# az_vert_evef.net
KiCad netlist of a schematic drawn in EAGLE
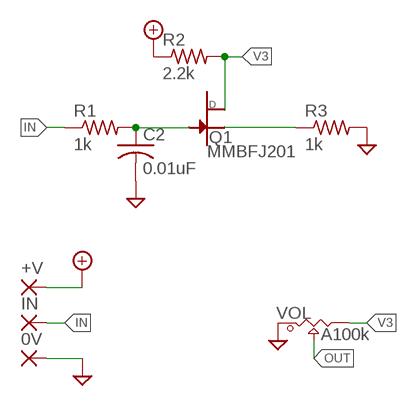
[diagram p0: schematic, sheet 1]

(export (version "E")
  (design (tool "Eeschema 10.0.6"))
  (components
    (comp (ref "+V")
      (value "SMD2")
      (footprint "eagle-import:SMD1,27-2,54")
      (libsource (lib "eagle-import") (part "SMD2"))
    )
    (comp (ref "0V")
      (value "SMD2")
      (footprint "eagle-import:SMD1,27-2,54")
      (libsource (lib "eagle-import") (part "SMD2"))
    )
    (comp (ref "C2")
      (value "0.01uF")
      (footprint "eagle-import:C0603")
      (libsource (lib "eagle-import") (part "C-USC0603"))
    )
    (comp (ref "IN")
      (value "SMD2")
      (footprint "eagle-import:SMD1,27-2,54")
      (libsource (lib "eagle-import") (part "SMD2"))
    )
    (comp (ref "Q1")
      (value "MMBFJ201")
      (footprint "eagle-import:MMBFJ201")
      (libsource (lib "eagle-import") (part "MMBFJ201"))
    )
    (comp (ref "R1")
      (value "1k")
      (footprint "eagle-import:R0603")
      (libsource (lib "eagle-import") (part "R-US_R0603"))
    )
    (comp (ref "R2")
      (value "2.2k")
      (footprint "eagle-import:R0603")
      (libsource (lib "eagle-import") (part "R-US_R0603"))
    )
    (comp (ref "R3")
      (value "1k")
      (footprint "eagle-import:R0603")
      (libsource (lib "eagle-import") (part "R-US_R0603"))
    )
    (comp (ref "VOL")
      (value "A100k")
      (footprint "eagle-import:POT_9MM_SMD")
      (libsource (lib "eagle-import") (part "POT_9MM_SMD"))
    )
  )
  (nets
    (net (code "1") (name "+9V") (class "Default")
      (node (ref "+V") (pin "1") (pinfunction "P_1") (pintype "passive"))
      (node (ref "R2") (pin "1") (pinfunction "1_1") (pintype "passive"))
    )
    (net (code "2") (name "GND") (class "Default")
      (node (ref "0V") (pin "1") (pinfunction "P_1") (pintype "passive"))
      (node (ref "C2") (pin "2") (pinfunction "2_2") (pintype "passive"))
      (node (ref "R3") (pin "2") (pinfunction "2_2") (pintype "passive"))
      (node (ref "VOL") (pin "1") (pinfunction "1_1") (pintype "bidirectional"))
    )
    (net (code "3") (name "IN") (class "Default")
      (node (ref "IN") (pin "1") (pinfunction "P_1") (pintype "passive"))
      (node (ref "R1") (pin "1") (pinfunction "1_1") (pintype "passive"))
    )
    (net (code "4") (name "Net-(C2-Pad1)") (class "Default")
      (node (ref "C2") (pin "1") (pinfunction "1_1") (pintype "passive"))
      (node (ref "Q1") (pin "G") (pinfunction "G_G") (pintype "bidirectional"))
      (node (ref "R1") (pin "2") (pinfunction "2_2") (pintype "passive"))
    )
    (net (code "5") (name "Net-(Q1-PadS)") (class "Default")
      (node (ref "Q1") (pin "S") (pinfunction "S_S") (pintype "bidirectional"))
      (node (ref "R3") (pin "1") (pinfunction "1_1") (pintype "passive"))
    )
    (net (code "6") (name "OUT") (class "Default")
      (node (ref "VOL") (pin "2") (pinfunction "2_2") (pintype "bidirectional"))
    )
    (net (code "7") (name "V3") (class "Default")
      (node (ref "Q1") (pin "D") (pinfunction "D_D") (pintype "bidirectional"))
      (node (ref "R2") (pin "2") (pinfunction "2_2") (pintype "passive"))
      (node (ref "VOL") (pin "3") (pinfunction "3_3") (pintype "bidirectional"))
    )
  )
)
